# motores_03.net
KiCad netlist of a schematic drawn in EAGLE
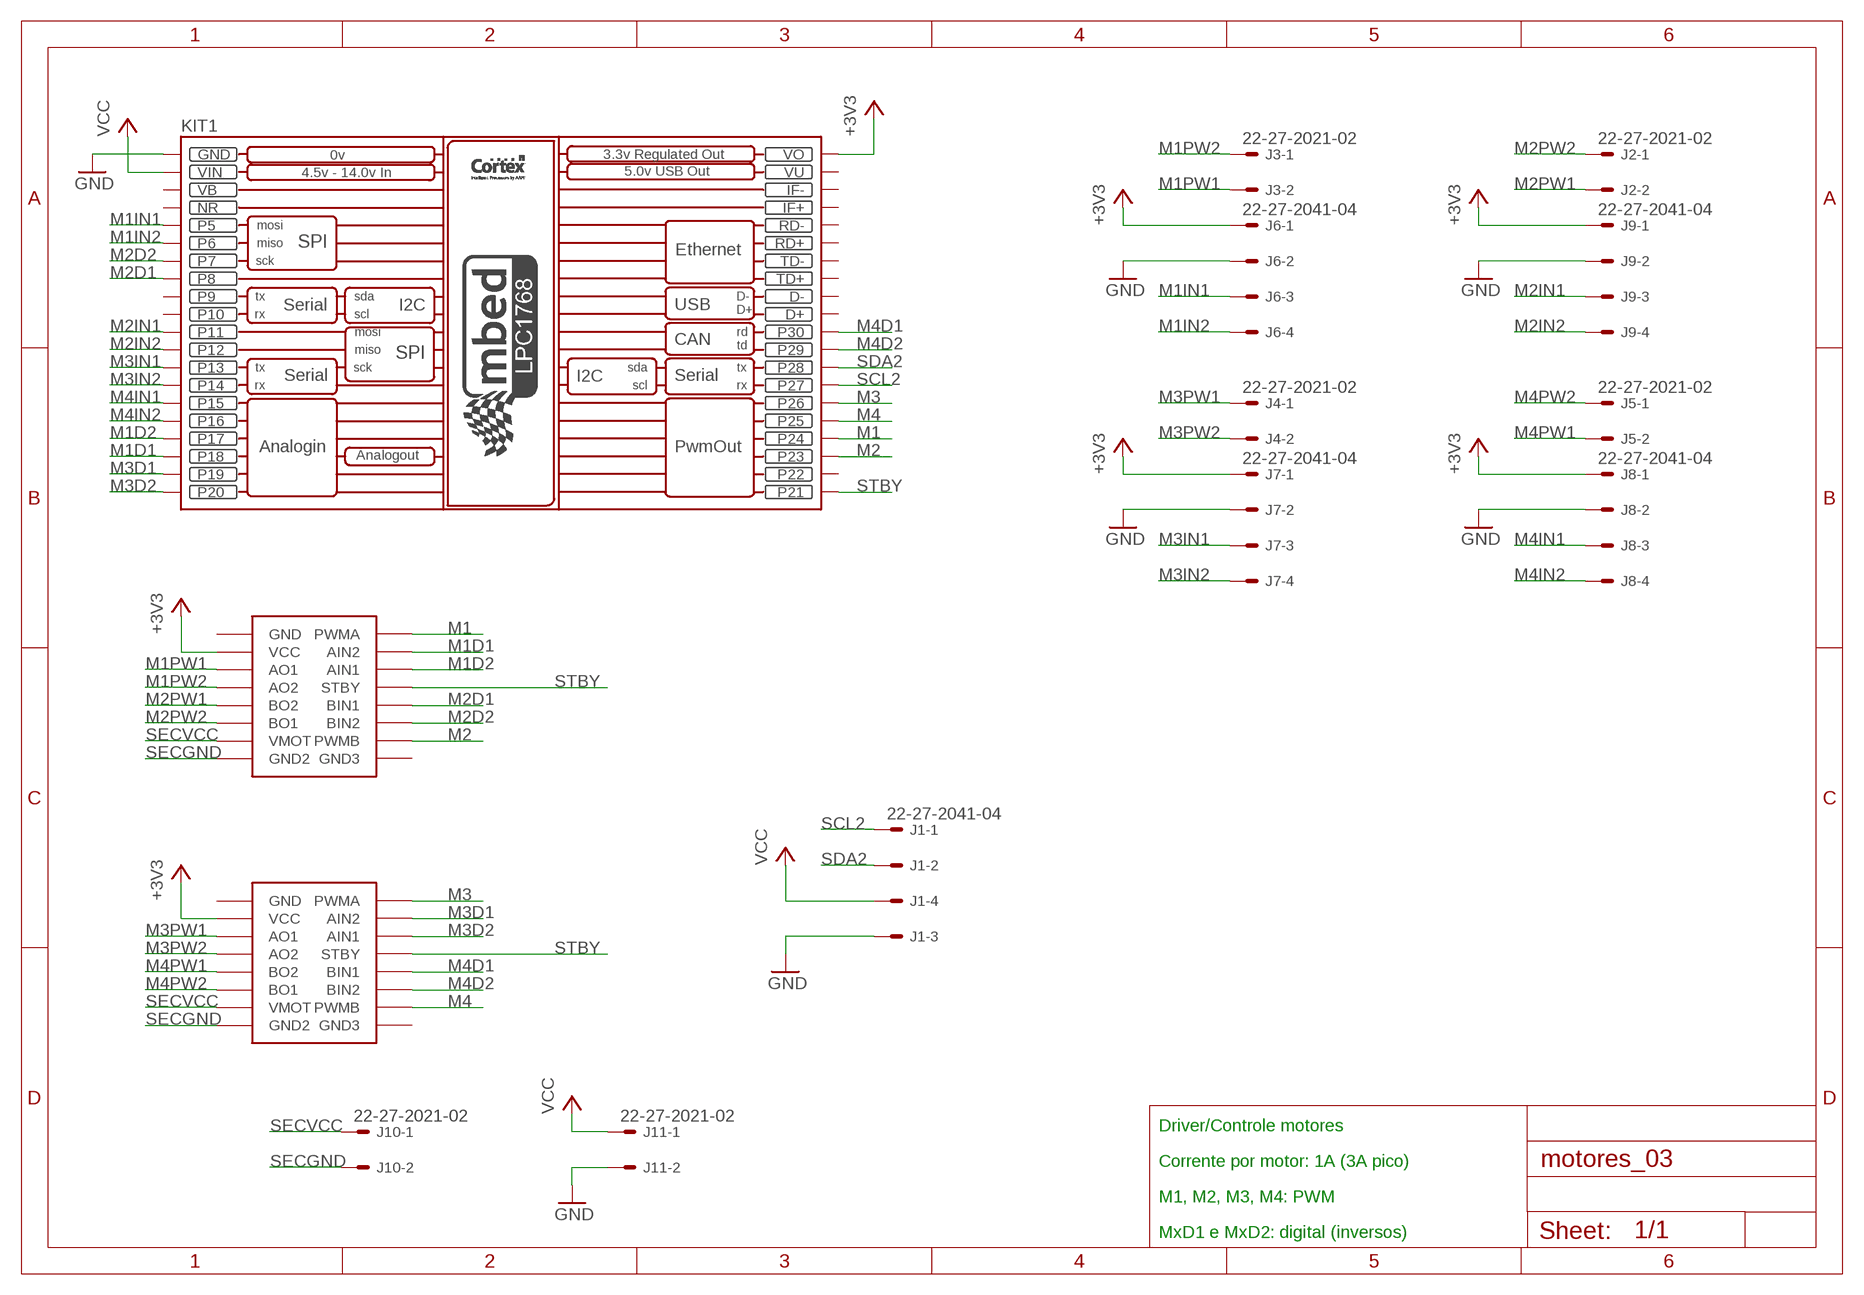
[diagram p0: schematic, sheet 1]

(export (version "E")
  (design (tool "Eeschema 10.0.6"))
  (components
    (comp (ref "J1")
      (value "22-27-2041-04")
      (footprint "eagle-import:6410-04")
      (libsource (lib "eagle-import") (part "22-?-0427-2041"))
    )
    (comp (ref "J2")
      (value "22-27-2021-02")
      (footprint "eagle-import:6410-02")
      (libsource (lib "eagle-import") (part "22-?-0227-2021"))
    )
    (comp (ref "J3")
      (value "22-27-2021-02")
      (footprint "eagle-import:6410-02")
      (libsource (lib "eagle-import") (part "22-?-0227-2021"))
    )
    (comp (ref "J4")
      (value "22-27-2021-02")
      (footprint "eagle-import:6410-02")
      (libsource (lib "eagle-import") (part "22-?-0227-2021"))
    )
    (comp (ref "J5")
      (value "22-27-2021-02")
      (footprint "eagle-import:6410-02")
      (libsource (lib "eagle-import") (part "22-?-0227-2021"))
    )
    (comp (ref "J6")
      (value "22-27-2041-04")
      (footprint "eagle-import:6410-04")
      (libsource (lib "eagle-import") (part "22-?-0427-2041"))
    )
    (comp (ref "J7")
      (value "22-27-2041-04")
      (footprint "eagle-import:6410-04")
      (libsource (lib "eagle-import") (part "22-?-0427-2041"))
    )
    (comp (ref "J8")
      (value "22-27-2041-04")
      (footprint "eagle-import:6410-04")
      (libsource (lib "eagle-import") (part "22-?-0427-2041"))
    )
    (comp (ref "J9")
      (value "22-27-2041-04")
      (footprint "eagle-import:6410-04")
      (libsource (lib "eagle-import") (part "22-?-0427-2041"))
    )
    (comp (ref "J10")
      (value "22-27-2021-02")
      (footprint "eagle-import:6410-02")
      (libsource (lib "eagle-import") (part "22-?-0227-2021"))
    )
    (comp (ref "J11")
      (value "22-27-2021-02")
      (footprint "eagle-import:6410-02")
      (libsource (lib "eagle-import") (part "22-?-0227-2021"))
    )
    (comp (ref "KIT1")
      (value "MBED_NXP_LPC1768")
      (footprint "eagle-import:MBED-KIT")
      (libsource (lib "eagle-import") (part "MBED_NXP_LPC1768"))
    )
    (comp (ref "U$1")
      (value "MOTORDRIVER")
      (footprint "eagle-import:16PH")
      (libsource (lib "eagle-import") (part "MOTORDRIVER"))
    )
    (comp (ref "U$2")
      (value "MOTORDRIVER")
      (footprint "eagle-import:16PH")
      (libsource (lib "eagle-import") (part "MOTORDRIVER"))
    )
  )
  (nets
    (net (code "1") (name "+3V3") (class "Default")
      (node (ref "J6") (pin "1") (pinfunction "S_1") (pintype "passive"))
      (node (ref "J7") (pin "1") (pinfunction "S_1") (pintype "passive"))
      (node (ref "J8") (pin "1") (pinfunction "S_1") (pintype "passive"))
      (node (ref "J9") (pin "1") (pinfunction "S_1") (pintype "passive"))
      (node (ref "KIT1") (pin "VOUT") (pinfunction "VO_VOUT") (pintype "power_in"))
      (node (ref "U$1") (pin "P$2") (pinfunction "VCC_P$2") (pintype "bidirectional"))
      (node (ref "U$2") (pin "P$2") (pinfunction "VCC_P$2") (pintype "bidirectional"))
    )
    (net (code "2") (name "/M1") (class "Default")
      (node (ref "KIT1") (pin "P$24") (pinfunction "P24_P$24") (pintype "bidirectional"))
      (node (ref "U$1") (pin "P$16") (pinfunction "PWMA_P$16") (pintype "bidirectional"))
    )
    (net (code "3") (name "/M1D1") (class "Default")
      (node (ref "KIT1") (pin "P$18") (pinfunction "P18_P$18") (pintype "bidirectional"))
      (node (ref "U$1") (pin "P$15") (pinfunction "AIN2_P$15") (pintype "bidirectional"))
    )
    (net (code "4") (name "/M1D2") (class "Default")
      (node (ref "KIT1") (pin "P$17") (pinfunction "P17_P$17") (pintype "bidirectional"))
      (node (ref "U$1") (pin "P$14") (pinfunction "AIN1_P$14") (pintype "bidirectional"))
    )
    (net (code "5") (name "/M1IN1") (class "Default")
      (node (ref "J6") (pin "3") (pinfunction "S_3") (pintype "passive"))
      (node (ref "KIT1") (pin "P$5") (pinfunction "P5_P$5") (pintype "bidirectional"))
    )
    (net (code "6") (name "/M1IN2") (class "Default")
      (node (ref "J6") (pin "4") (pinfunction "S_4") (pintype "passive"))
      (node (ref "KIT1") (pin "P$6") (pinfunction "P6_P$6") (pintype "bidirectional"))
    )
    (net (code "7") (name "/M1PW1") (class "Default")
      (node (ref "J3") (pin "2") (pinfunction "S_2") (pintype "passive"))
      (node (ref "U$1") (pin "P$3") (pinfunction "AO1_P$3") (pintype "bidirectional"))
    )
    (net (code "8") (name "/M1PW2") (class "Default")
      (node (ref "J3") (pin "1") (pinfunction "S_1") (pintype "passive"))
      (node (ref "U$1") (pin "P$4") (pinfunction "AO2_P$4") (pintype "bidirectional"))
    )
    (net (code "9") (name "/M2") (class "Default")
      (node (ref "KIT1") (pin "P$23") (pinfunction "P23_P$23") (pintype "bidirectional"))
      (node (ref "U$1") (pin "P$10") (pinfunction "PWMB_P$10") (pintype "bidirectional"))
    )
    (net (code "10") (name "/M2D1") (class "Default")
      (node (ref "KIT1") (pin "P$8") (pinfunction "P8_P$8") (pintype "bidirectional"))
      (node (ref "U$1") (pin "P$12") (pinfunction "BIN1_P$12") (pintype "bidirectional"))
    )
    (net (code "11") (name "/M2D2") (class "Default")
      (node (ref "KIT1") (pin "P$7") (pinfunction "P7_P$7") (pintype "bidirectional"))
      (node (ref "U$1") (pin "P$11") (pinfunction "BIN2_P$11") (pintype "bidirectional"))
    )
    (net (code "12") (name "/M2IN1") (class "Default")
      (node (ref "J9") (pin "3") (pinfunction "S_3") (pintype "passive"))
      (node (ref "KIT1") (pin "P$11") (pinfunction "P11_P$11") (pintype "bidirectional"))
    )
    (net (code "13") (name "/M2IN2") (class "Default")
      (node (ref "J9") (pin "4") (pinfunction "S_4") (pintype "passive"))
      (node (ref "KIT1") (pin "P$12") (pinfunction "P12_P$12") (pintype "bidirectional"))
    )
    (net (code "14") (name "/M2PW1") (class "Default")
      (node (ref "J2") (pin "2") (pinfunction "S_2") (pintype "passive"))
      (node (ref "U$1") (pin "P$5") (pinfunction "BO2_P$5") (pintype "bidirectional"))
    )
    (net (code "15") (name "/M2PW2") (class "Default")
      (node (ref "J2") (pin "1") (pinfunction "S_1") (pintype "passive"))
      (node (ref "U$1") (pin "P$6") (pinfunction "BO1_P$6") (pintype "bidirectional"))
    )
    (net (code "16") (name "/M3") (class "Default")
      (node (ref "KIT1") (pin "P$26") (pinfunction "P26_P$26") (pintype "bidirectional"))
      (node (ref "U$2") (pin "P$16") (pinfunction "PWMA_P$16") (pintype "bidirectional"))
    )
    (net (code "17") (name "/M3D1") (class "Default")
      (node (ref "KIT1") (pin "P$19") (pinfunction "P19_P$19") (pintype "bidirectional"))
      (node (ref "U$2") (pin "P$15") (pinfunction "AIN2_P$15") (pintype "bidirectional"))
    )
    (net (code "18") (name "/M3D2") (class "Default")
      (node (ref "KIT1") (pin "P$20") (pinfunction "P20_P$20") (pintype "bidirectional"))
      (node (ref "U$2") (pin "P$14") (pinfunction "AIN1_P$14") (pintype "bidirectional"))
    )
    (net (code "19") (name "/M3IN1") (class "Default")
      (node (ref "J7") (pin "3") (pinfunction "S_3") (pintype "passive"))
      (node (ref "KIT1") (pin "P$13") (pinfunction "P13_P$13") (pintype "bidirectional"))
    )
    (net (code "20") (name "/M3IN2") (class "Default")
      (node (ref "J7") (pin "4") (pinfunction "S_4") (pintype "passive"))
      (node (ref "KIT1") (pin "P$14") (pinfunction "P14_P$14") (pintype "bidirectional"))
    )
    (net (code "21") (name "/M3PW1") (class "Default")
      (node (ref "J4") (pin "1") (pinfunction "S_1") (pintype "passive"))
      (node (ref "U$2") (pin "P$3") (pinfunction "AO1_P$3") (pintype "bidirectional"))
    )
    (net (code "22") (name "/M3PW2") (class "Default")
      (node (ref "J4") (pin "2") (pinfunction "S_2") (pintype "passive"))
      (node (ref "U$2") (pin "P$4") (pinfunction "AO2_P$4") (pintype "bidirectional"))
    )
    (net (code "23") (name "/M4") (class "Default")
      (node (ref "KIT1") (pin "P$25") (pinfunction "P25_P$25") (pintype "bidirectional"))
      (node (ref "U$2") (pin "P$10") (pinfunction "PWMB_P$10") (pintype "bidirectional"))
    )
    (net (code "24") (name "/M4D1") (class "Default")
      (node (ref "KIT1") (pin "P$30") (pinfunction "P30_P$30") (pintype "bidirectional"))
      (node (ref "U$2") (pin "P$12") (pinfunction "BIN1_P$12") (pintype "bidirectional"))
    )
    (net (code "25") (name "/M4D2") (class "Default")
      (node (ref "KIT1") (pin "P$29") (pinfunction "P29_P$29") (pintype "bidirectional"))
      (node (ref "U$2") (pin "P$11") (pinfunction "BIN2_P$11") (pintype "bidirectional"))
    )
    (net (code "26") (name "/M4IN1") (class "Default")
      (node (ref "J8") (pin "3") (pinfunction "S_3") (pintype "passive"))
      (node (ref "KIT1") (pin "P$15") (pinfunction "P15_P$15") (pintype "bidirectional"))
    )
    (net (code "27") (name "/M4IN2") (class "Default")
      (node (ref "J8") (pin "4") (pinfunction "S_4") (pintype "passive"))
      (node (ref "KIT1") (pin "P$16") (pinfunction "P16_P$16") (pintype "bidirectional"))
    )
    (net (code "28") (name "/M4PW1") (class "Default")
      (node (ref "J5") (pin "2") (pinfunction "S_2") (pintype "passive"))
      (node (ref "U$2") (pin "P$5") (pinfunction "BO2_P$5") (pintype "bidirectional"))
    )
    (net (code "29") (name "/M4PW2") (class "Default")
      (node (ref "J5") (pin "1") (pinfunction "S_1") (pintype "passive"))
      (node (ref "U$2") (pin "P$6") (pinfunction "BO1_P$6") (pintype "bidirectional"))
    )
    (net (code "30") (name "/NR") (class "Default")
      (node (ref "KIT1") (pin "NR") (pinfunction "NR_NR") (pintype "power_in"))
    )
    (net (code "31") (name "/SCL2") (class "Default")
      (node (ref "J1") (pin "1") (pinfunction "S_1") (pintype "passive"))
      (node (ref "KIT1") (pin "P$27") (pinfunction "P27_P$27") (pintype "bidirectional"))
    )
    (net (code "32") (name "/SDA2") (class "Default")
      (node (ref "J1") (pin "2") (pinfunction "S_2") (pintype "passive"))
      (node (ref "KIT1") (pin "P$28") (pinfunction "P28_P$28") (pintype "bidirectional"))
    )
    (net (code "33") (name "/SECGND") (class "Default")
      (node (ref "J10") (pin "2") (pinfunction "S_2") (pintype "passive"))
      (node (ref "U$1") (pin "P$8") (pinfunction "GND2_P$8") (pintype "bidirectional"))
      (node (ref "U$2") (pin "P$8") (pinfunction "GND2_P$8") (pintype "bidirectional"))
    )
    (net (code "34") (name "/SECVCC") (class "Default")
      (node (ref "J10") (pin "1") (pinfunction "S_1") (pintype "passive"))
      (node (ref "U$1") (pin "P$7") (pinfunction "VMOT_P$7") (pintype "bidirectional"))
      (node (ref "U$2") (pin "P$7") (pinfunction "VMOT_P$7") (pintype "bidirectional"))
    )
    (net (code "35") (name "/STBY") (class "Default")
      (node (ref "KIT1") (pin "P$21") (pinfunction "P21_P$21") (pintype "bidirectional"))
      (node (ref "U$1") (pin "P$13") (pinfunction "STBY_P$13") (pintype "bidirectional"))
      (node (ref "U$2") (pin "P$13") (pinfunction "STBY_P$13") (pintype "bidirectional"))
    )
    (net (code "36") (name "/VB") (class "Default")
      (node (ref "KIT1") (pin "VB") (pinfunction "VB_VB") (pintype "power_in"))
    )
    (net (code "37") (name "/VU") (class "Default")
      (node (ref "KIT1") (pin "VU") (pinfunction "VU_VU") (pintype "power_in"))
    )
    (net (code "38") (name "GND") (class "Default")
      (node (ref "J1") (pin "3") (pinfunction "S_3") (pintype "passive"))
      (node (ref "J11") (pin "2") (pinfunction "S_2") (pintype "passive"))
      (node (ref "J6") (pin "2") (pinfunction "S_2") (pintype "passive"))
      (node (ref "J7") (pin "2") (pinfunction "S_2") (pintype "passive"))
      (node (ref "J8") (pin "2") (pinfunction "S_2") (pintype "passive"))
      (node (ref "J9") (pin "2") (pinfunction "S_2") (pintype "passive"))
      (node (ref "KIT1") (pin "GND") (pinfunction "GND_GND") (pintype "power_in"))
    )
    (net (code "39") (name "VCC") (class "Default")
      (node (ref "J1") (pin "4") (pinfunction "S_4") (pintype "passive"))
      (node (ref "J11") (pin "1") (pinfunction "S_1") (pintype "passive"))
      (node (ref "KIT1") (pin "VIN") (pinfunction "VIN_VIN") (pintype "power_in"))
    )
    (net (code "40") (name "unconnected-(KIT1-P9-PadP$9)") (class "Default")
      (node (ref "KIT1") (pin "P$9") (pinfunction "P9_P$9") (pintype "bidirectional"))
    )
    (net (code "41") (name "unconnected-(KIT1-P10-PadP$10)") (class "Default")
      (node (ref "KIT1") (pin "P$10") (pinfunction "P10_P$10") (pintype "bidirectional"))
    )
    (net (code "42") (name "unconnected-(KIT1-P22-PadP$22)") (class "Default")
      (node (ref "KIT1") (pin "P$22") (pinfunction "P22_P$22") (pintype "bidirectional"))
    )
    (net (code "43") (name "unconnected-(KIT1-PadD+)") (class "Default")
      (node (ref "KIT1") (pin "D+") (pinfunction "D+_D+") (pintype "bidirectional"))
    )
    (net (code "44") (name "unconnected-(KIT1-PadD-)") (class "Default")
      (node (ref "KIT1") (pin "D-") (pinfunction "D-_D-") (pintype "bidirectional"))
    )
    (net (code "45") (name "unconnected-(KIT1-PadIF+)") (class "Default")
      (node (ref "KIT1") (pin "IF+") (pinfunction "IF+_IF+") (pintype "bidirectional"))
    )
    (net (code "46") (name "unconnected-(KIT1-PadIF-)") (class "Default")
      (node (ref "KIT1") (pin "IF-") (pinfunction "IF-_IF-") (pintype "bidirectional"))
    )
    (net (code "47") (name "unconnected-(KIT1-PadRD+)") (class "Default")
      (node (ref "KIT1") (pin "RD+") (pinfunction "RD+_RD+") (pintype "bidirectional"))
    )
    (net (code "48") (name "unconnected-(KIT1-PadRD-)") (class "Default")
      (node (ref "KIT1") (pin "RD-") (pinfunction "RD-_RD-") (pintype "bidirectional"))
    )
    (net (code "49") (name "unconnected-(KIT1-PadTD+)") (class "Default")
      (node (ref "KIT1") (pin "TD+") (pinfunction "TD+_TD+") (pintype "bidirectional"))
    )
    (net (code "50") (name "unconnected-(KIT1-PadTD-)") (class "Default")
      (node (ref "KIT1") (pin "TD-") (pinfunction "TD-_TD-") (pintype "bidirectional"))
    )
    (net (code "51") (name "unconnected-(U$1-GND-PadP$1)") (class "Default")
      (node (ref "U$1") (pin "P$1") (pinfunction "GND_P$1") (pintype "bidirectional"))
    )
    (net (code "52") (name "unconnected-(U$1-GND3-PadP$9)") (class "Default")
      (node (ref "U$1") (pin "P$9") (pinfunction "GND3_P$9") (pintype "bidirectional"))
    )
    (net (code "53") (name "unconnected-(U$2-GND-PadP$1)") (class "Default")
      (node (ref "U$2") (pin "P$1") (pinfunction "GND_P$1") (pintype "bidirectional"))
    )
    (net (code "54") (name "unconnected-(U$2-GND3-PadP$9)") (class "Default")
      (node (ref "U$2") (pin "P$9") (pinfunction "GND3_P$9") (pintype "bidirectional"))
    )
  )
)
